# Attenuator_Proto.net
KiCad netlist of a schematic drawn in Altium Designer
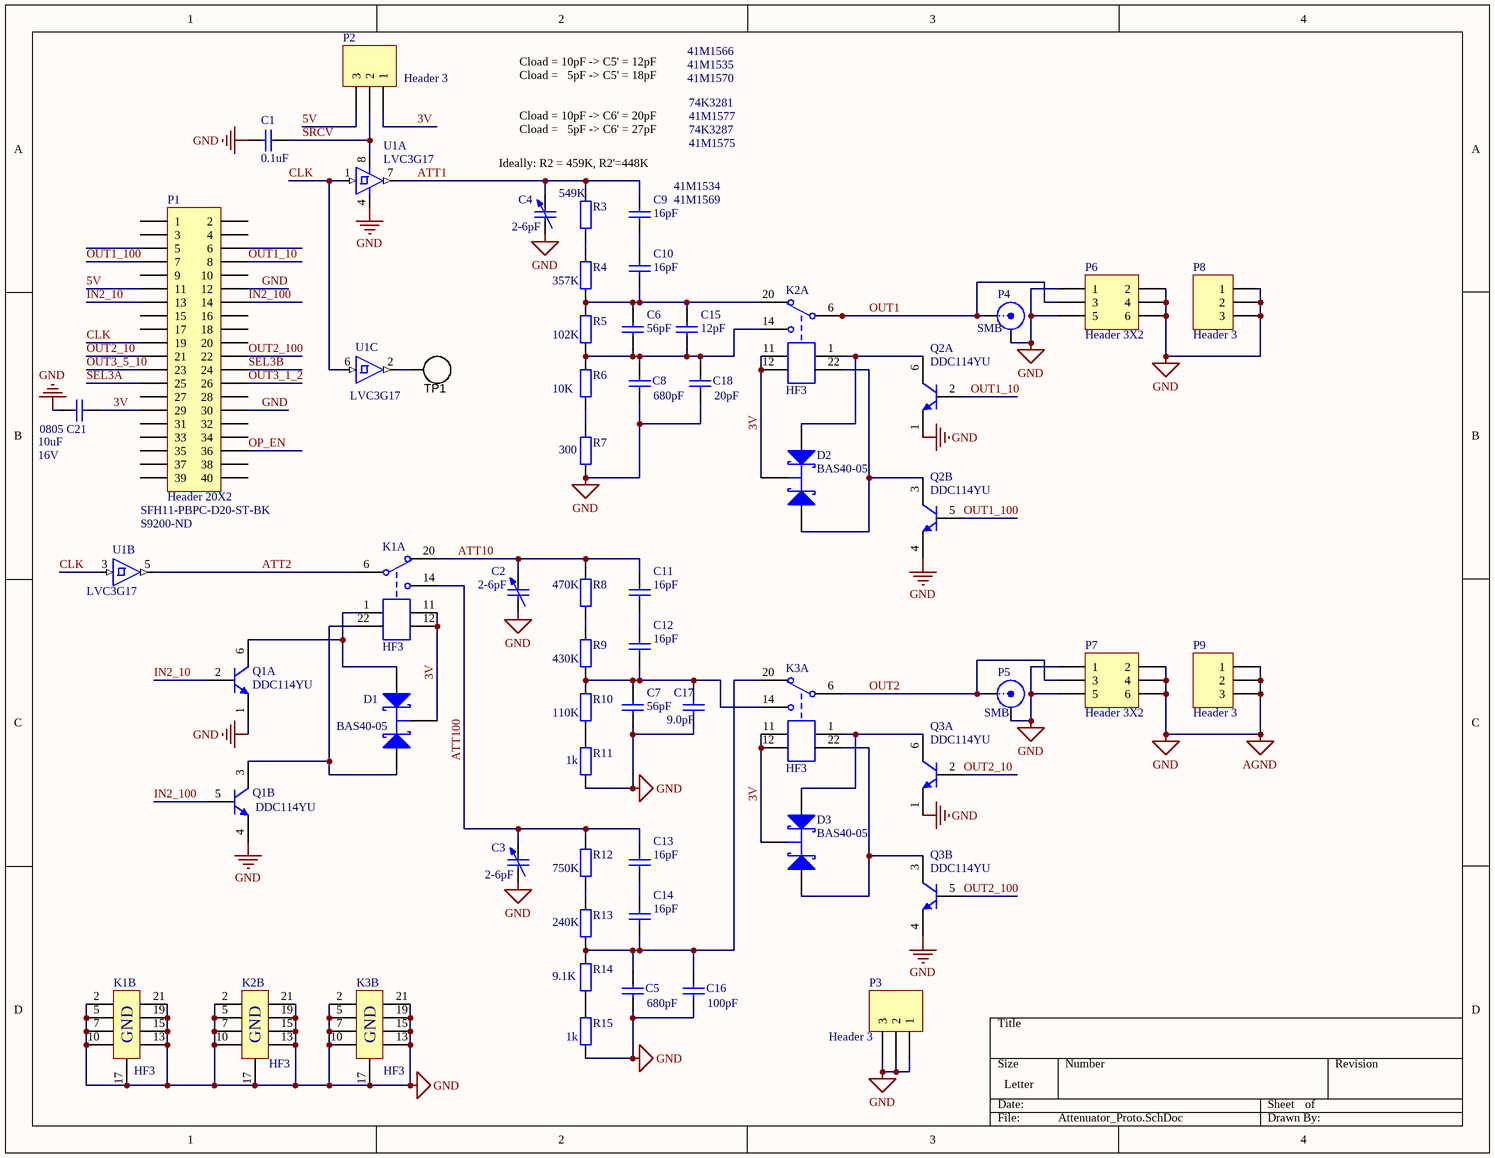
[diagram p0: Attenuator_Proto.SchDoc]

(export (version "E")
  (design (tool "Eeschema 10.0.6"))
  (components
    (comp (ref "C1")
      (value "0.1uF")
      (footprint "C0805")
      (description "Capacitor")
      (fields (field (name "Comment") "Cap") (field (name "PUBLISHER") "Altium Limited"))
      (libsource (lib "Miscellaneous Devices") (part "Cap"))
    )
    (comp (ref "C2")
      (value "2-6pF")
      (footprint "CAPC3225N")
      (description "Variable or Adjustable Capacitor")
      (fields (field (name "Comment") "Cap Var") (field (name "PUBLISHER") "Altium Limited"))
      (libsource (lib "Miscellaneous Devices") (part "Cap Var"))
    )
    (comp (ref "C3")
      (value "2-6pF")
      (footprint "CAPC3225N")
      (description "Variable or Adjustable Capacitor")
      (fields (field (name "Comment") "Cap Var") (field (name "PUBLISHER") "Altium Limited"))
      (libsource (lib "Miscellaneous Devices") (part "Cap Var"))
    )
    (comp (ref "C4")
      (value "2-6pF")
      (footprint "CAPC3225N")
      (description "Variable or Adjustable Capacitor")
      (fields (field (name "Comment") "Cap Var") (field (name "PUBLISHER") "Altium Limited"))
      (libsource (lib "Miscellaneous Devices") (part "Cap Var"))
    )
    (comp (ref "C5")
      (value "680pF")
      (footprint "c0805")
      (description "Capacitor")
      (fields (field (name "Comment") "Cap") (field (name "PUBLISHER") "Altium Limited"))
      (libsource (lib "Miscellaneous Devices") (part "Cap"))
    )
    (comp (ref "C6")
      (value "56pF")
      (footprint "c0805")
      (description "Capacitor")
      (fields (field (name "Comment") "Cap") (field (name "PUBLISHER") "Altium Limited"))
      (libsource (lib "Miscellaneous Devices") (part "Cap"))
    )
    (comp (ref "C7")
      (value "56pF")
      (footprint "c0805")
      (description "Capacitor")
      (fields (field (name "Comment") "Cap") (field (name "PUBLISHER") "Altium Limited"))
      (libsource (lib "Miscellaneous Devices") (part "Cap"))
    )
    (comp (ref "C8")
      (value "680pF")
      (footprint "c0805")
      (description "Capacitor")
      (fields (field (name "Comment") "Cap") (field (name "PUBLISHER") "Altium Limited"))
      (libsource (lib "Miscellaneous Devices") (part "Cap"))
    )
    (comp (ref "C9")
      (value "16pF")
      (footprint "c0805")
      (description "Capacitor")
      (fields
        (field (name "SUPPLIER PART NUMBER 1") "41M1569")
        (field (name "SUPPLIER PART NUMBER 2") "41M1534")
        (field (name "Comment") "Cap")
        (field (name "PUBLISHER") "Altium Limited")
      )
      (libsource (lib "Miscellaneous Devices") (part "Cap"))
    )
    (comp (ref "C10")
      (value "16pF")
      (footprint "c0805")
      (description "Capacitor")
      (fields (field (name "Comment") "Cap") (field (name "PUBLISHER") "Altium Limited"))
      (libsource (lib "Miscellaneous Devices") (part "Cap"))
    )
    (comp (ref "C11")
      (value "16pF")
      (footprint "c0805")
      (description "Capacitor")
      (fields (field (name "Comment") "Cap") (field (name "PUBLISHER") "Altium Limited"))
      (libsource (lib "Miscellaneous Devices") (part "Cap"))
    )
    (comp (ref "C12")
      (value "16pF")
      (footprint "c0805")
      (description "Capacitor")
      (fields (field (name "Comment") "Cap") (field (name "PUBLISHER") "Altium Limited"))
      (libsource (lib "Miscellaneous Devices") (part "Cap"))
    )
    (comp (ref "C13")
      (value "16pF")
      (footprint "c0805")
      (description "Capacitor")
      (fields (field (name "Comment") "Cap") (field (name "PUBLISHER") "Altium Limited"))
      (libsource (lib "Miscellaneous Devices") (part "Cap"))
    )
    (comp (ref "C14")
      (value "16pF")
      (footprint "c0805")
      (description "Capacitor")
      (fields (field (name "Comment") "Cap") (field (name "PUBLISHER") "Altium Limited"))
      (libsource (lib "Miscellaneous Devices") (part "Cap"))
    )
    (comp (ref "C15")
      (value "12pF")
      (footprint "c0805")
      (description "Capacitor")
      (fields
        (field (name "SUPPLIER PART NUMBER 2") "41M1570")
        (field (name "SUPPLIER PART NUMBER 1") "41M1535")
        (field (name "SUPPLIER PART NUMBER 3") "41M1566")
        (field (name "Comment") "Cap")
        (field (name "PUBLISHER") "Altium Limited")
      )
      (libsource (lib "Miscellaneous Devices") (part "Cap"))
    )
    (comp (ref "C16")
      (value "100pF")
      (footprint "c0805")
      (description "Capacitor")
      (fields (field (name "Comment") "Cap") (field (name "PUBLISHER") "Altium Limited"))
      (libsource (lib "Miscellaneous Devices") (part "Cap"))
    )
    (comp (ref "C17")
      (value "9.0pF")
      (footprint "c0805")
      (description "Capacitor")
      (fields (field (name "Comment") "Cap") (field (name "PUBLISHER") "Altium Limited"))
      (libsource (lib "Miscellaneous Devices") (part "Cap"))
    )
    (comp (ref "C18")
      (value "20pF")
      (footprint "c0805")
      (description "Capacitor")
      (fields
        (field (name "SUPPLIER PART NUMBER 1") "41M1575")
        (field (name "SUPPLIER PART NUMBER 2") "74K3287")
        (field (name "SUPPLIER PART NUMBER 3") "41M1577")
        (field (name "SUPPLIER PART NUMBER 4") "74K3281")
        (field (name "Comment") "Cap")
        (field (name "PUBLISHER") "Altium Limited")
      )
      (libsource (lib "Miscellaneous Devices") (part "Cap"))
    )
    (comp (ref "C21")
      (value "10uF")
      (footprint "CAPC2512L")
      (description "Capacitor (Semiconductor SIM Model)")
      (fields
        (field (name "PACKAGEREFERENCE") "0805")
        (field (name "VOLTAGE") "16V")
        (field (name "MANUFACTURER") "Murata")
        (field (name "PARTNUMBER") "GRM21BF51C106ZE15L")
        (field (name "PUBLISHER") "Altium Limited")
      )
      (libsource (lib "Miscellaneous Devices") (part "Cap Semi"))
    )
    (comp (ref "D1")
      (value "BAS40-05")
      (footprint "SOT-23")
      (description "Silicon AF Schottky Diode for High-Speed Switching")
      (fields (field (name "PUBLISHER") "Altium Limited"))
      (libsource (lib "Infineon Discrete Diode") (part "BAS40-05"))
    )
    (comp (ref "D2")
      (value "BAS40-05")
      (footprint "SOT-23")
      (description "Silicon AF Schottky Diode for High-Speed Switching")
      (fields (field (name "PUBLISHER") "Altium Limited"))
      (libsource (lib "Infineon Discrete Diode") (part "BAS40-05"))
    )
    (comp (ref "D3")
      (value "BAS40-05")
      (footprint "SOT-23")
      (description "Silicon AF Schottky Diode for High-Speed Switching")
      (fields (field (name "PUBLISHER") "Altium Limited"))
      (libsource (lib "Infineon Discrete Diode") (part "BAS40-05"))
    )
    (comp (ref "K1")
      (value "HF3_2coils_latching")
      (footprint "HF3-75_Ohm")
      (description "HF3 Relay, Latching type, 2 coils")
      (fields (field (name "MANUFACTURER") "Tyco Electronics") (field (name "PARTNUMBER") "HF3"))
      (libsource (lib "Chudik") (part "HF3_2coils_latching"))
    )
    (comp (ref "K2")
      (value "HF3_2coils_latching")
      (footprint "HF3-75_Ohm")
      (description "HF3 Relay, Latching type, 2 coils")
      (fields (field (name "MANUFACTURER") "Tyco Electronics") (field (name "PARTNUMBER") "HF3"))
      (libsource (lib "") (part "HF3_2coils_latching_1"))
    )
    (comp (ref "K3")
      (value "HF3_2coils_latching")
      (footprint "HF3-75_Ohm")
      (description "HF3 Relay, Latching type, 2 coils")
      (fields (field (name "MANUFACTURER") "Tyco Electronics") (field (name "PARTNUMBER") "HF3"))
      (libsource (lib "Chudik") (part "HF3_2coils_latching"))
    )
    (comp (ref "P1")
      (value "Header 20X2")
      (footprint "HDR2X20")
      (description "Header, 20-Pin, Dual row")
      (fields
        (field (name "PARTNUMBER") "SFH11-PBPC-D20-ST-BK")
        (field (name "SUPPLIER PART NUMBER 1") "S9200-ND")
        (field (name "PUBLISHER") "Altium Limited")
      )
      (libsource (lib "Miscellaneous Connectors") (part "Header 20X2"))
    )
    (comp (ref "P2")
      (value "Header 3")
      (footprint "HDR1X3")
      (description "Header, 3-Pin")
      (fields (field (name "PUBLISHER") "Altium Limited"))
      (libsource (lib "") (part "Header 3_2"))
    )
    (comp (ref "P3")
      (value "Header 3")
      (footprint "HDR1X3")
      (description "Header, 3-Pin")
      (fields (field (name "PUBLISHER") "Altium Limited"))
      (libsource (lib "Miscellaneous Connectors") (part "Header 3"))
    )
    (comp (ref "P4")
      (value "SMB")
      (footprint "SMB_V-RJ45")
      (description "SMB Straight Connector")
      (fields (field (name "PUBLISHER") "Altium Limited"))
      (libsource (lib "Miscellaneous Connectors") (part "SMB"))
    )
    (comp (ref "P5")
      (value "SMB")
      (footprint "SMB_V-RJ45")
      (description "SMB Straight Connector")
      (fields (field (name "PUBLISHER") "Altium Limited"))
      (libsource (lib "Miscellaneous Connectors") (part "SMB"))
    )
    (comp (ref "P6")
      (value "Header 3X2")
      (footprint "HDR2X3")
      (description "Header, 3-Pin, Dual row")
      (fields (field (name "PUBLISHER") "Altium Limited"))
      (libsource (lib "Miscellaneous Connectors") (part "Header 3X2"))
    )
    (comp (ref "P7")
      (value "Header 3X2")
      (footprint "HDR2X3")
      (description "Header, 3-Pin, Dual row")
      (fields (field (name "PUBLISHER") "Altium Limited"))
      (libsource (lib "Miscellaneous Connectors") (part "Header 3X2"))
    )
    (comp (ref "P8")
      (value "Header 3")
      (footprint "HDR1X3")
      (description "Header, 3-Pin")
      (fields (field (name "PUBLISHER") "Altium Limited"))
      (libsource (lib "") (part "Header 3_1"))
    )
    (comp (ref "P9")
      (value "Header 3")
      (footprint "HDR1X3")
      (description "Header, 3-Pin")
      (fields (field (name "PUBLISHER") "Altium Limited"))
      (libsource (lib "") (part "Header 3_1"))
    )
    (comp (ref "Q1")
      (value "DDCxxxxU")
      (footprint "SOT-363")
      (description "NPN PRE-BIASED SMALL SIGNAL DUAL SURFACE MOUNT TRANSISTOR")
      (fields (field (name "PARTNUMBER") "DDC114YU"))
      (libsource (lib "iXBT") (part "DDCxxxxU"))
    )
    (comp (ref "Q2")
      (value "DDCxxxxU")
      (footprint "SOT-363")
      (description "NPN PRE-BIASED SMALL SIGNAL DUAL SURFACE MOUNT TRANSISTOR")
      (fields (field (name "PARTNUMBER") "DDC114YU"))
      (libsource (lib "iXBT") (part "DDCxxxxU"))
    )
    (comp (ref "Q3")
      (value "DDCxxxxU")
      (footprint "SOT-363")
      (description "NPN PRE-BIASED SMALL SIGNAL DUAL SURFACE MOUNT TRANSISTOR")
      (fields (field (name "PARTNUMBER") "DDC114YU"))
      (libsource (lib "iXBT") (part "DDCxxxxU"))
    )
    (comp (ref "R3")
      (value "549K")
      (footprint "0805")
      (description "Resistor")
      (fields (field (name "Comment") "Res2") (field (name "PUBLISHER") "Altium Limited"))
      (libsource (lib "Miscellaneous Devices") (part "Res2"))
    )
    (comp (ref "R4")
      (value "357K")
      (footprint "0805")
      (description "Resistor")
      (fields (field (name "Comment") "Res2") (field (name "PUBLISHER") "Altium Limited"))
      (libsource (lib "Miscellaneous Devices") (part "Res2"))
    )
    (comp (ref "R5")
      (value "102K")
      (footprint "0805")
      (description "Resistor")
      (fields (field (name "Comment") "Res2") (field (name "PUBLISHER") "Altium Limited"))
      (libsource (lib "Miscellaneous Devices") (part "Res2"))
    )
    (comp (ref "R6")
      (value "10K")
      (footprint "0805")
      (description "Resistor")
      (fields (field (name "Comment") "Res2") (field (name "PUBLISHER") "Altium Limited"))
      (libsource (lib "Miscellaneous Devices") (part "Res2"))
    )
    (comp (ref "R7")
      (value "300")
      (footprint "0805")
      (description "Resistor")
      (fields (field (name "Comment") "Res2") (field (name "PUBLISHER") "Altium Limited"))
      (libsource (lib "Miscellaneous Devices") (part "Res2"))
    )
    (comp (ref "R8")
      (value "470K")
      (footprint "0805")
      (description "Resistor")
      (fields (field (name "Comment") "Res2") (field (name "PUBLISHER") "Altium Limited"))
      (libsource (lib "Miscellaneous Devices") (part "Res2"))
    )
    (comp (ref "R9")
      (value "430K")
      (footprint "0805")
      (description "Resistor")
      (fields (field (name "Comment") "Res2") (field (name "PUBLISHER") "Altium Limited"))
      (libsource (lib "Miscellaneous Devices") (part "Res2"))
    )
    (comp (ref "R10")
      (value "110K")
      (footprint "0805")
      (description "Resistor")
      (fields (field (name "Comment") "Res2") (field (name "PUBLISHER") "Altium Limited"))
      (libsource (lib "Miscellaneous Devices") (part "Res2"))
    )
    (comp (ref "R11")
      (value "1k")
      (footprint "0805")
      (description "Resistor")
      (fields (field (name "Comment") "Res2") (field (name "PUBLISHER") "Altium Limited"))
      (libsource (lib "Miscellaneous Devices") (part "Res2"))
    )
    (comp (ref "R12")
      (value "750K")
      (footprint "0805")
      (description "Resistor")
      (fields (field (name "Comment") "Res2") (field (name "PUBLISHER") "Altium Limited"))
      (libsource (lib "Miscellaneous Devices") (part "Res2"))
    )
    (comp (ref "R13")
      (value "240K")
      (footprint "0805")
      (description "Resistor")
      (fields (field (name "Comment") "Res2") (field (name "PUBLISHER") "Altium Limited"))
      (libsource (lib "Miscellaneous Devices") (part "Res2"))
    )
    (comp (ref "R14")
      (value "9.1K")
      (footprint "0805")
      (description "Resistor")
      (fields (field (name "Comment") "Res2") (field (name "PUBLISHER") "Altium Limited"))
      (libsource (lib "Miscellaneous Devices") (part "Res2"))
    )
    (comp (ref "R15")
      (value "1k")
      (footprint "0805")
      (description "Resistor")
      (fields (field (name "Comment") "Res2") (field (name "PUBLISHER") "Altium Limited"))
      (libsource (lib "Miscellaneous Devices") (part "Res2"))
    )
    (comp (ref "TP1")
      (value "TESTPOINT")
      (footprint "TESTPOINT")
      (description "TEST POINT.  No entry in BOM.")
      (libsource (lib "NSC MiscParts") (part "TESTPOINT"))
    )
    (comp (ref "U1")
      (value "LVC3G17")
      (footprint "sm8")
      (fields
        (field (name "MANUFACTURER") "Texas Instruments")
        (field (name "MANUFACTURER PART NUMBER") "SN74LVC3G17DCTR")
      )
      (libsource (lib "VIVENG_Library") (part "SN74LVC3G17DCTR"))
    )
  )
  (nets
    (net (code "1") (name "/3V") (class "Default")
      (node (ref "C21") (pin "1") (pinfunction "1_1") (pintype "passive"))
      (node (ref "D1") (pin "3") (pinfunction "K_3") (pintype "passive"))
      (node (ref "D2") (pin "3") (pinfunction "K_3") (pintype "passive"))
      (node (ref "D3") (pin "3") (pinfunction "K_3") (pintype "passive"))
      (node (ref "K1") (pin "11") (pinfunction "11_11") (pintype "passive"))
      (node (ref "K1") (pin "12") (pinfunction "12_12") (pintype "passive"))
      (node (ref "K2") (pin "11") (pinfunction "11_11") (pintype "passive"))
      (node (ref "K2") (pin "12") (pinfunction "12_12") (pintype "passive"))
      (node (ref "K3") (pin "11") (pinfunction "11_11") (pintype "passive"))
      (node (ref "K3") (pin "12") (pinfunction "12_12") (pintype "passive"))
      (node (ref "P1") (pin "29") (pinfunction "29_29") (pintype "passive"))
      (node (ref "P2") (pin "1") (pinfunction "1_1") (pintype "passive"))
    )
    (net (code "2") (name "/5V") (class "Default")
      (node (ref "P1") (pin "11") (pinfunction "11_11") (pintype "passive"))
      (node (ref "P2") (pin "3") (pinfunction "3_3") (pintype "passive"))
    )
    (net (code "3") (name "/ATT1") (class "Default")
      (node (ref "C4") (pin "2") (pinfunction "2_2") (pintype "passive"))
      (node (ref "C9") (pin "2") (pinfunction "2_2") (pintype "passive"))
      (node (ref "R3") (pin "2") (pinfunction "2_2") (pintype "passive"))
      (node (ref "U1") (pin "7") (pinfunction "1Y_7") (pintype "output"))
    )
    (net (code "4") (name "/ATT2") (class "Default")
      (node (ref "K1") (pin "6") (pinfunction "6_6") (pintype "passive"))
      (node (ref "U1") (pin "5") (pinfunction "2Y_5") (pintype "output"))
    )
    (net (code "5") (name "/ATT10") (class "Default")
      (node (ref "C11") (pin "2") (pinfunction "2_2") (pintype "passive"))
      (node (ref "C2") (pin "2") (pinfunction "2_2") (pintype "passive"))
      (node (ref "K1") (pin "20") (pinfunction "20_20") (pintype "passive"))
      (node (ref "R8") (pin "2") (pinfunction "2_2") (pintype "passive"))
    )
    (net (code "6") (name "/ATT100") (class "Default")
      (node (ref "C13") (pin "2") (pinfunction "2_2") (pintype "passive"))
      (node (ref "C3") (pin "2") (pinfunction "2_2") (pintype "passive"))
      (node (ref "K1") (pin "14") (pinfunction "14_14") (pintype "passive"))
      (node (ref "R12") (pin "2") (pinfunction "2_2") (pintype "passive"))
    )
    (net (code "7") (name "/CLK") (class "Default")
      (node (ref "P1") (pin "19") (pinfunction "19_19") (pintype "passive"))
      (node (ref "U1") (pin "1") (pinfunction "1A_1") (pintype "input"))
      (node (ref "U1") (pin "3") (pinfunction "2A_3") (pintype "input"))
      (node (ref "U1") (pin "6") (pinfunction "3A_6") (pintype "input"))
    )
    (net (code "8") (name "/IN2_10") (class "Default")
      (node (ref "P1") (pin "13") (pinfunction "13_13") (pintype "passive"))
      (node (ref "Q1") (pin "2") (pinfunction "B_2") (pintype "passive"))
    )
    (net (code "9") (name "/IN2_100") (class "Default")
      (node (ref "P1") (pin "14") (pinfunction "14_14") (pintype "passive"))
      (node (ref "Q1") (pin "5") (pinfunction "B_5") (pintype "passive"))
    )
    (net (code "10") (name "/OP_EN") (class "Default")
      (node (ref "P1") (pin "36") (pinfunction "36_36") (pintype "passive"))
    )
    (net (code "11") (name "/OUT1") (class "Default")
      (node (ref "K2") (pin "6") (pinfunction "6_6") (pintype "passive"))
      (node (ref "P4") (pin "1") (pinfunction "X_1") (pintype "passive"))
      (node (ref "P6") (pin "3") (pinfunction "3_3") (pintype "passive"))
    )
    (net (code "12") (name "/OUT1_10") (class "Default")
      (node (ref "P1") (pin "8") (pinfunction "8_8") (pintype "passive"))
      (node (ref "Q2") (pin "2") (pinfunction "B_2") (pintype "passive"))
    )
    (net (code "13") (name "/OUT1_100") (class "Default")
      (node (ref "P1") (pin "7") (pinfunction "7_7") (pintype "passive"))
      (node (ref "Q2") (pin "5") (pinfunction "B_5") (pintype "passive"))
    )
    (net (code "14") (name "/OUT2") (class "Default")
      (node (ref "K3") (pin "6") (pinfunction "6_6") (pintype "passive"))
      (node (ref "P5") (pin "1") (pinfunction "X_1") (pintype "passive"))
      (node (ref "P7") (pin "3") (pinfunction "3_3") (pintype "passive"))
    )
    (net (code "15") (name "/OUT2_10") (class "Default")
      (node (ref "P1") (pin "21") (pinfunction "21_21") (pintype "passive"))
      (node (ref "Q3") (pin "2") (pinfunction "B_2") (pintype "passive"))
    )
    (net (code "16") (name "/OUT2_100") (class "Default")
      (node (ref "P1") (pin "22") (pinfunction "22_22") (pintype "passive"))
      (node (ref "Q3") (pin "5") (pinfunction "B_5") (pintype "passive"))
    )
    (net (code "17") (name "/OUT3_1_2") (class "Default")
      (node (ref "P1") (pin "26") (pinfunction "26_26") (pintype "passive"))
    )
    (net (code "18") (name "/OUT3_5_10") (class "Default")
      (node (ref "P1") (pin "23") (pinfunction "23_23") (pintype "passive"))
    )
    (net (code "19") (name "/SEL3A") (class "Default")
      (node (ref "P1") (pin "25") (pinfunction "25_25") (pintype "passive"))
    )
    (net (code "20") (name "/SEL3B") (class "Default")
      (node (ref "P1") (pin "24") (pinfunction "24_24") (pintype "passive"))
    )
    (net (code "21") (name "/SRCV") (class "Default")
      (node (ref "C1") (pin "1") (pinfunction "1_1") (pintype "passive"))
      (node (ref "P2") (pin "2") (pinfunction "2_2") (pintype "passive"))
      (node (ref "U1") (pin "8") (pinfunction "VCC_8") (pintype "power_in"))
    )
    (net (code "22") (name "AGND") (class "Default")
      (node (ref "C1") (pin "2") (pinfunction "2_2") (pintype "passive"))
      (node (ref "C16") (pin "1") (pinfunction "1_1") (pintype "passive"))
      (node (ref "C17") (pin "1") (pinfunction "1_1") (pintype "passive"))
      (node (ref "C18") (pin "1") (pinfunction "1_1") (pintype "passive"))
      (node (ref "C2") (pin "1") (pinfunction "1_1") (pintype "passive"))
      (node (ref "C21") (pin "2") (pinfunction "2_2") (pintype "passive"))
      (node (ref "C3") (pin "1") (pinfunction "1_1") (pintype "passive"))
      (node (ref "C4") (pin "1") (pinfunction "1_1") (pintype "passive"))
      (node (ref "C5") (pin "1") (pinfunction "1_1") (pintype "passive"))
      (node (ref "C7") (pin "1") (pinfunction "1_1") (pintype "passive"))
      (node (ref "C8") (pin "1") (pinfunction "1_1") (pintype "passive"))
      (node (ref "K1") (pin "10") (pinfunction "GND_10") (pintype "power_in"))
      (node (ref "K1") (pin "13") (pinfunction "GND_13") (pintype "power_in"))
      (node (ref "K1") (pin "15") (pinfunction "GND_15") (pintype "power_in"))
      (node (ref "K1") (pin "17") (pinfunction "GND_17") (pintype "power_in"))
      (node (ref "K1") (pin "19") (pinfunction "GND_19") (pintype "power_in"))
      (node (ref "K1") (pin "2") (pinfunction "GND_2") (pintype "power_in"))
      (node (ref "K1") (pin "21") (pinfunction "GND_21") (pintype "power_in"))
      (node (ref "K1") (pin "5") (pinfunction "GND_5") (pintype "power_in"))
      (node (ref "K1") (pin "7") (pinfunction "GND_7") (pintype "power_in"))
      (node (ref "K2") (pin "10") (pinfunction "GND_10") (pintype "power_in"))
      (node (ref "K2") (pin "13") (pinfunction "GND_13") (pintype "power_in"))
      (node (ref "K2") (pin "15") (pinfunction "GND_15") (pintype "power_in"))
      (node (ref "K2") (pin "17") (pinfunction "GND_17") (pintype "power_in"))
      (node (ref "K2") (pin "19") (pinfunction "GND_19") (pintype "power_in"))
      (node (ref "K2") (pin "2") (pinfunction "GND_2") (pintype "power_in"))
      (node (ref "K2") (pin "21") (pinfunction "GND_21") (pintype "power_in"))
      (node (ref "K2") (pin "5") (pinfunction "GND_5") (pintype "power_in"))
      (node (ref "K2") (pin "7") (pinfunction "GND_7") (pintype "power_in"))
      (node (ref "K3") (pin "10") (pinfunction "GND_10") (pintype "power_in"))
      (node (ref "K3") (pin "13") (pinfunction "GND_13") (pintype "power_in"))
      (node (ref "K3") (pin "15") (pinfunction "GND_15") (pintype "power_in"))
      (node (ref "K3") (pin "17") (pinfunction "GND_17") (pintype "power_in"))
      (node (ref "K3") (pin "19") (pinfunction "GND_19") (pintype "power_in"))
      (node (ref "K3") (pin "2") (pinfunction "GND_2") (pintype "power_in"))
      (node (ref "K3") (pin "21") (pinfunction "GND_21") (pintype "power_in"))
      (node (ref "K3") (pin "5") (pinfunction "GND_5") (pintype "power_in"))
      (node (ref "K3") (pin "7") (pinfunction "GND_7") (pintype "power_in"))
      (node (ref "P1") (pin "12") (pinfunction "12_12") (pintype "passive"))
      (node (ref "P1") (pin "30") (pinfunction "30_30") (pintype "passive"))
      (node (ref "P3") (pin "1") (pinfunction "1_1") (pintype "passive"))
      (node (ref "P3") (pin "2") (pinfunction "2_2") (pintype "passive"))
      (node (ref "P3") (pin "3") (pinfunction "3_3") (pintype "passive"))
      (node (ref "P4") (pin "2") (pinfunction "Y_2") (pintype "passive"))
      (node (ref "P5") (pin "2") (pinfunction "Y_2") (pintype "passive"))
      (node (ref "P6") (pin "1") (pinfunction "1_1") (pintype "passive"))
      (node (ref "P6") (pin "2") (pinfunction "2_2") (pintype "passive"))
      (node (ref "P6") (pin "4") (pinfunction "4_4") (pintype "passive"))
      (node (ref "P6") (pin "5") (pinfunction "5_5") (pintype "passive"))
      (node (ref "P6") (pin "6") (pinfunction "6_6") (pintype "passive"))
      (node (ref "P7") (pin "1") (pinfunction "1_1") (pintype "passive"))
      (node (ref "P7") (pin "2") (pinfunction "2_2") (pintype "passive"))
      (node (ref "P7") (pin "4") (pinfunction "4_4") (pintype "passive"))
      (node (ref "P7") (pin "5") (pinfunction "5_5") (pintype "passive"))
      (node (ref "P7") (pin "6") (pinfunction "6_6") (pintype "passive"))
      (node (ref "P8") (pin "1") (pinfunction "1_1") (pintype "passive"))
      (node (ref "P8") (pin "2") (pinfunction "2_2") (pintype "passive"))
      (node (ref "P8") (pin "3") (pinfunction "3_3") (pintype "passive"))
      (node (ref "P9") (pin "1") (pinfunction "1_1") (pintype "passive"))
      (node (ref "P9") (pin "2") (pinfunction "2_2") (pintype "passive"))
      (node (ref "P9") (pin "3") (pinfunction "3_3") (pintype "passive"))
      (node (ref "Q1") (pin "1") (pinfunction "E_1") (pintype "passive"))
      (node (ref "Q1") (pin "4") (pinfunction "E_4") (pintype "passive"))
      (node (ref "Q2") (pin "1") (pinfunction "E_1") (pintype "passive"))
      (node (ref "Q2") (pin "4") (pinfunction "E_4") (pintype "passive"))
      (node (ref "Q3") (pin "1") (pinfunction "E_1") (pintype "passive"))
      (node (ref "Q3") (pin "4") (pinfunction "E_4") (pintype "passive"))
      (node (ref "R11") (pin "1") (pinfunction "1_1") (pintype "passive"))
      (node (ref "R15") (pin "1") (pinfunction "1_1") (pintype "passive"))
      (node (ref "R7") (pin "1") (pinfunction "1_1") (pintype "passive"))
      (node (ref "U1") (pin "4") (pinfunction "GND_4") (pintype "power_in"))
    )
    (net (code "23") (name "Net-(C10-Pad1)") (class "Default")
      (node (ref "C10") (pin "1") (pinfunction "1_1") (pintype "passive"))
      (node (ref "C15") (pin "2") (pinfunction "2_2") (pintype "passive"))
      (node (ref "C6") (pin "2") (pinfunction "2_2") (pintype "passive"))
      (node (ref "K2") (pin "20") (pinfunction "20_20") (pintype "passive"))
      (node (ref "R4") (pin "1") (pinfunction "1_1") (pintype "passive"))
      (node (ref "R5") (pin "2") (pinfunction "2_2") (pintype "passive"))
    )
    (net (code "24") (name "Net-(C10-Pad2)") (class "Default")
      (node (ref "C10") (pin "2") (pinfunction "2_2") (pintype "passive"))
      (node (ref "C9") (pin "1") (pinfunction "1_1") (pintype "passive"))
    )
    (net (code "25") (name "Net-(C11-Pad1)") (class "Default")
      (node (ref "C11") (pin "1") (pinfunction "1_1") (pintype "passive"))
      (node (ref "C12") (pin "2") (pinfunction "2_2") (pintype "passive"))
    )
    (net (code "26") (name "Net-(C12-Pad1)") (class "Default")
      (node (ref "C12") (pin "1") (pinfunction "1_1") (pintype "passive"))
      (node (ref "C17") (pin "2") (pinfunction "2_2") (pintype "passive"))
      (node (ref "C7") (pin "2") (pinfunction "2_2") (pintype "passive"))
      (node (ref "K3") (pin "14") (pinfunction "14_14") (pintype "passive"))
      (node (ref "R10") (pin "2") (pinfunction "2_2") (pintype "passive"))
      (node (ref "R9") (pin "1") (pinfunction "1_1") (pintype "passive"))
    )
    (net (code "27") (name "Net-(C13-Pad1)") (class "Default")
      (node (ref "C13") (pin "1") (pinfunction "1_1") (pintype "passive"))
      (node (ref "C14") (pin "2") (pinfunction "2_2") (pintype "passive"))
    )
    (net (code "28") (name "Net-(C14-Pad1)") (class "Default")
      (node (ref "C14") (pin "1") (pinfunction "1_1") (pintype "passive"))
      (node (ref "C16") (pin "2") (pinfunction "2_2") (pintype "passive"))
      (node (ref "C5") (pin "2") (pinfunction "2_2") (pintype "passive"))
      (node (ref "K3") (pin "20") (pinfunction "20_20") (pintype "passive"))
      (node (ref "R13") (pin "1") (pinfunction "1_1") (pintype "passive"))
      (node (ref "R14") (pin "2") (pinfunction "2_2") (pintype "passive"))
    )
    (net (code "29") (name "Net-(C15-Pad1)") (class "Default")
      (node (ref "C15") (pin "1") (pinfunction "1_1") (pintype "passive"))
      (node (ref "C18") (pin "2") (pinfunction "2_2") (pintype "passive"))
      (node (ref "C6") (pin "1") (pinfunction "1_1") (pintype "passive"))
      (node (ref "C8") (pin "2") (pinfunction "2_2") (pintype "passive"))
      (node (ref "K2") (pin "14") (pinfunction "14_14") (pintype "passive"))
      (node (ref "R5") (pin "1") (pinfunction "1_1") (pintype "passive"))
      (node (ref "R6") (pin "2") (pinfunction "2_2") (pintype "passive"))
    )
    (net (code "30") (name "Net-(D1-A1)") (class "Default")
      (node (ref "D1") (pin "1") (pinfunction "A1_1") (pintype "passive"))
      (node (ref "K1") (pin "1") (pinfunction "1_1") (pintype "passive"))
      (node (ref "Q1") (pin "6") (pinfunction "C_6") (pintype "passive"))
    )
    (net (code "31") (name "Net-(D1-A2)") (class "Default")
      (node (ref "D1") (pin "2") (pinfunction "A2_2") (pintype "passive"))
      (node (ref "K1") (pin "22") (pinfunction "22_22") (pintype "passive"))
      (node (ref "Q1") (pin "3") (pinfunction "C_3") (pintype "passive"))
    )
    (net (code "32") (name "Net-(D2-A1)") (class "Default")
      (node (ref "D2") (pin "1") (pinfunction "A1_1") (pintype "passive"))
      (node (ref "K2") (pin "1") (pinfunction "1_1") (pintype "passive"))
      (node (ref "Q2") (pin "6") (pinfunction "C_6") (pintype "passive"))
    )
    (net (code "33") (name "Net-(D2-A2)") (class "Default")
      (node (ref "D2") (pin "2") (pinfunction "A2_2") (pintype "passive"))
      (node (ref "K2") (pin "22") (pinfunction "22_22") (pintype "passive"))
      (node (ref "Q2") (pin "3") (pinfunction "C_3") (pintype "passive"))
    )
    (net (code "34") (name "Net-(D3-A1)") (class "Default")
      (node (ref "D3") (pin "1") (pinfunction "A1_1") (pintype "passive"))
      (node (ref "K3") (pin "1") (pinfunction "1_1") (pintype "passive"))
      (node (ref "Q3") (pin "6") (pinfunction "C_6") (pintype "passive"))
    )
    (net (code "35") (name "Net-(D3-A2)") (class "Default")
      (node (ref "D3") (pin "2") (pinfunction "A2_2") (pintype "passive"))
      (node (ref "K3") (pin "22") (pinfunction "22_22") (pintype "passive"))
      (node (ref "Q3") (pin "3") (pinfunction "C_3") (pintype "passive"))
    )
    (net (code "36") (name "Net-(R3-Pad1)") (class "Default")
      (node (ref "R3") (pin "1") (pinfunction "1_1") (pintype "passive"))
      (node (ref "R4") (pin "2") (pinfunction "2_2") (pintype "passive"))
    )
    (net (code "37") (name "Net-(R6-Pad1)") (class "Default")
      (node (ref "R6") (pin "1") (pinfunction "1_1") (pintype "passive"))
      (node (ref "R7") (pin "2") (pinfunction "2_2") (pintype "passive"))
    )
    (net (code "38") (name "Net-(R8-Pad1)") (class "Default")
      (node (ref "R8") (pin "1") (pinfunction "1_1") (pintype "passive"))
      (node (ref "R9") (pin "2") (pinfunction "2_2") (pintype "passive"))
    )
    (net (code "39") (name "Net-(R10-Pad1)") (class "Default")
      (node (ref "R10") (pin "1") (pinfunction "1_1") (pintype "passive"))
      (node (ref "R11") (pin "2") (pinfunction "2_2") (pintype "passive"))
    )
    (net (code "40") (name "Net-(R12-Pad1)") (class "Default")
      (node (ref "R12") (pin "1") (pinfunction "1_1") (pintype "passive"))
      (node (ref "R13") (pin "2") (pinfunction "2_2") (pintype "passive"))
    )
    (net (code "41") (name "Net-(R14-Pad1)") (class "Default")
      (node (ref "R14") (pin "1") (pinfunction "1_1") (pintype "passive"))
      (node (ref "R15") (pin "2") (pinfunction "2_2") (pintype "passive"))
    )
    (net (code "42") (name "Net-(U1C-3Y)") (class "Default")
      (node (ref "TP1") (pin "1") (pintype "passive"))
      (node (ref "U1") (pin "2") (pinfunction "3Y_2") (pintype "output"))
    )
    (net (code "43") (name "unconnected-(P1-Pad1)") (class "Default")
      (node (ref "P1") (pin "1") (pinfunction "1_1") (pintype "passive"))
    )
    (net (code "44") (name "unconnected-(P1-Pad2)") (class "Default")
      (node (ref "P1") (pin "2") (pinfunction "2_2") (pintype "passive"))
    )
    (net (code "45") (name "unconnected-(P1-Pad3)") (class "Default")
      (node (ref "P1") (pin "3") (pinfunction "3_3") (pintype "passive"))
    )
    (net (code "46") (name "unconnected-(P1-Pad4)") (class "Default")
      (node (ref "P1") (pin "4") (pinfunction "4_4") (pintype "passive"))
    )
    (net (code "47") (name "unconnected-(P1-Pad5)") (class "Default")
      (node (ref "P1") (pin "5") (pinfunction "5_5") (pintype "passive"))
    )
    (net (code "48") (name "unconnected-(P1-Pad6)") (class "Default")
      (node (ref "P1") (pin "6") (pinfunction "6_6") (pintype "passive"))
    )
    (net (code "49") (name "unconnected-(P1-Pad9)") (class "Default")
      (node (ref "P1") (pin "9") (pinfunction "9_9") (pintype "passive"))
    )
    (net (code "50") (name "unconnected-(P1-Pad10)") (class "Default")
      (node (ref "P1") (pin "10") (pinfunction "10_10") (pintype "passive"))
    )
    (net (code "51") (name "unconnected-(P1-Pad15)") (class "Default")
      (node (ref "P1") (pin "15") (pinfunction "15_15") (pintype "passive"))
    )
    (net (code "52") (name "unconnected-(P1-Pad16)") (class "Default")
      (node (ref "P1") (pin "16") (pinfunction "16_16") (pintype "passive"))
    )
    (net (code "53") (name "unconnected-(P1-Pad17)") (class "Default")
      (node (ref "P1") (pin "17") (pinfunction "17_17") (pintype "passive"))
    )
    (net (code "54") (name "unconnected-(P1-Pad18)") (class "Default")
      (node (ref "P1") (pin "18") (pinfunction "18_18") (pintype "passive"))
    )
    (net (code "55") (name "unconnected-(P1-Pad20)") (class "Default")
      (node (ref "P1") (pin "20") (pinfunction "20_20") (pintype "passive"))
    )
    (net (code "56") (name "unconnected-(P1-Pad27)") (class "Default")
      (node (ref "P1") (pin "27") (pinfunction "27_27") (pintype "passive"))
    )
    (net (code "57") (name "unconnected-(P1-Pad28)") (class "Default")
      (node (ref "P1") (pin "28") (pinfunction "28_28") (pintype "passive"))
    )
    (net (code "58") (name "unconnected-(P1-Pad31)") (class "Default")
      (node (ref "P1") (pin "31") (pinfunction "31_31") (pintype "passive"))
    )
    (net (code "59") (name "unconnected-(P1-Pad32)") (class "Default")
      (node (ref "P1") (pin "32") (pinfunction "32_32") (pintype "passive"))
    )
    (net (code "60") (name "unconnected-(P1-Pad33)") (class "Default")
      (node (ref "P1") (pin "33") (pinfunction "33_33") (pintype "passive"))
    )
    (net (code "61") (name "unconnected-(P1-Pad34)") (class "Default")
      (node (ref "P1") (pin "34") (pinfunction "34_34") (pintype "passive"))
    )
    (net (code "62") (name "unconnected-(P1-Pad35)") (class "Default")
      (node (ref "P1") (pin "35") (pinfunction "35_35") (pintype "passive"))
    )
    (net (code "63") (name "unconnected-(P1-Pad37)") (class "Default")
      (node (ref "P1") (pin "37") (pinfunction "37_37") (pintype "passive"))
    )
    (net (code "64") (name "unconnected-(P1-Pad38)") (class "Default")
      (node (ref "P1") (pin "38") (pinfunction "38_38") (pintype "passive"))
    )
    (net (code "65") (name "unconnected-(P1-Pad39)") (class "Default")
      (node (ref "P1") (pin "39") (pinfunction "39_39") (pintype "passive"))
    )
    (net (code "66") (name "unconnected-(P1-Pad40)") (class "Default")
      (node (ref "P1") (pin "40") (pinfunction "40_40") (pintype "passive"))
    )
  )
)
